# Schematic.net
KiCad netlist of a schematic drawn in EAGLE
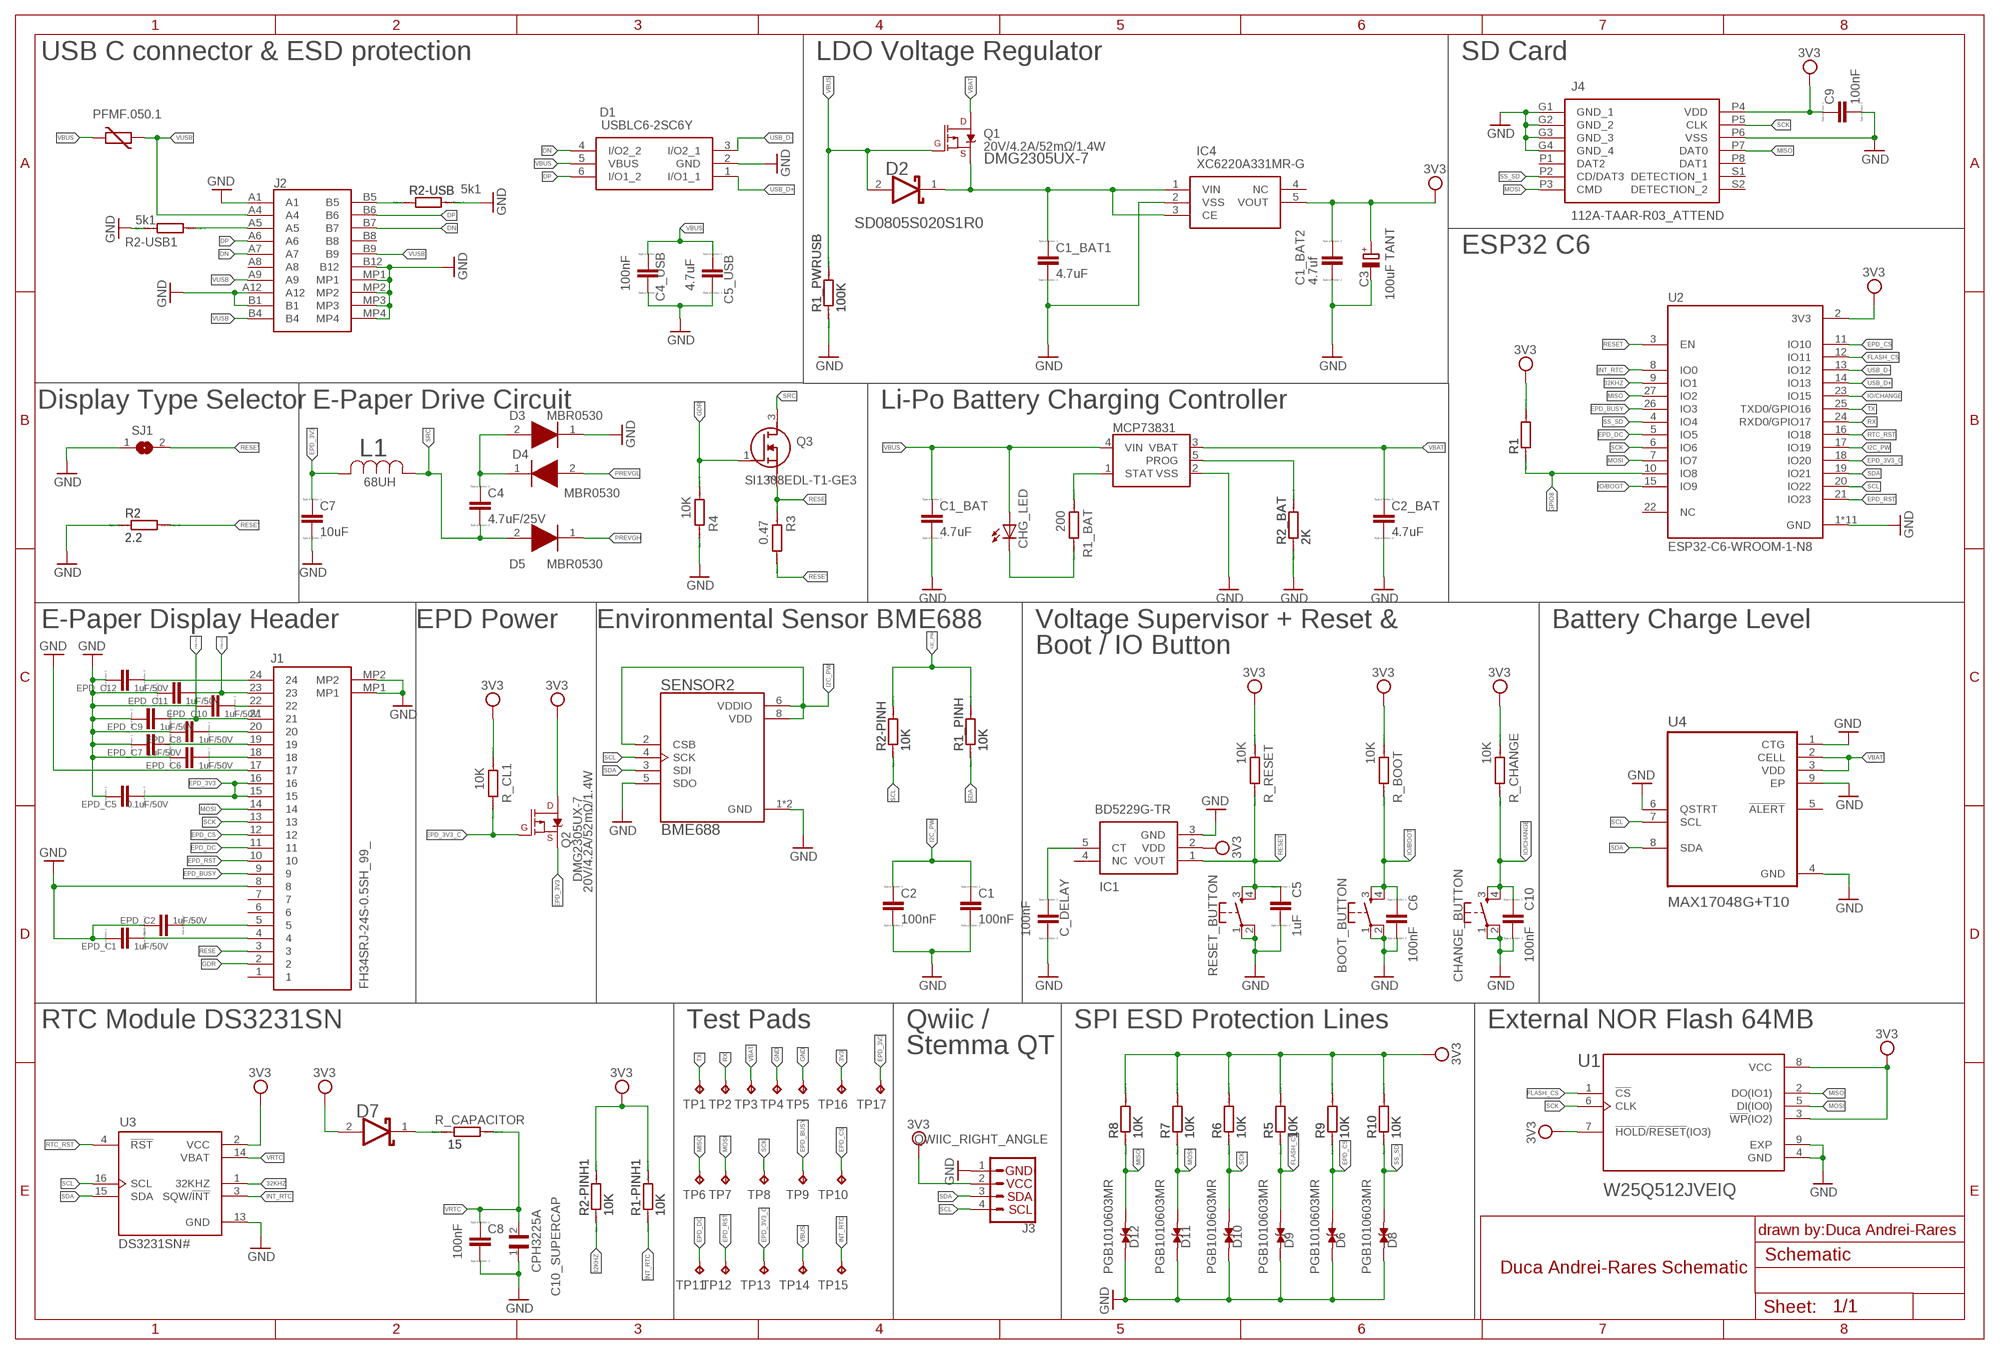
[diagram p0: schematic, sheet 1]

(export (version "E")
  (design (tool "Eeschema 10.0.6"))
  (components
    (comp (ref "BOOT_BUTTON")
      (value "BUTTON_CUSYOMV1")
      (footprint "eagle-import:MYBUTTON")
      (libsource (lib "eagle-import") (part "BUTTON_CUSYOMV1"))
    )
    (comp (ref "C1")
      (value "100nF")
      (footprint "eagle-import:EAGLE-LTSPICE_C0402")
      (libsource (lib "eagle-import") (part "EAGLE-LTSPICE_CC0402"))
    )
    (comp (ref "C1_BAT")
      (value "4.7uF")
      (footprint "eagle-import:EAGLE-LTSPICE_C0402")
      (libsource (lib "eagle-import") (part "EAGLE-LTSPICE_CC0402"))
    )
    (comp (ref "C1_BAT1")
      (value "4.7uF")
      (footprint "eagle-import:EAGLE-LTSPICE_C0402")
      (libsource (lib "eagle-import") (part "EAGLE-LTSPICE_CC0402"))
    )
    (comp (ref "C1_BAT2")
      (value "4.7uf")
      (footprint "eagle-import:EAGLE-LTSPICE_C0402")
      (libsource (lib "eagle-import") (part "EAGLE-LTSPICE_CC0402"))
    )
    (comp (ref "C2")
      (value "100nF")
      (footprint "eagle-import:EAGLE-LTSPICE_C0402")
      (libsource (lib "eagle-import") (part "EAGLE-LTSPICE_CC0402"))
    )
    (comp (ref "C2_BAT")
      (value "4.7uF")
      (footprint "eagle-import:EAGLE-LTSPICE_C0402")
      (libsource (lib "eagle-import") (part "EAGLE-LTSPICE_CC0402"))
    )
    (comp (ref "C3")
      (value "100uF TANT")
      (footprint "eagle-import:RCL_CT3528")
      (libsource (lib "eagle-import") (part "RCL_CPOL-EUCT3528"))
    )
    (comp (ref "C4")
      (value "4.7uF/25V")
      (footprint "eagle-import:EAGLE-LTSPICE_C0402")
      (libsource (lib "eagle-import") (part "EAGLE-LTSPICE_CC0402"))
    )
    (comp (ref "C4_USB")
      (value "100nF")
      (footprint "eagle-import:EAGLE-LTSPICE_C0402")
      (libsource (lib "eagle-import") (part "EAGLE-LTSPICE_CC0402"))
    )
    (comp (ref "C5")
      (value "1uF")
      (footprint "eagle-import:EAGLE-LTSPICE_C0402")
      (libsource (lib "eagle-import") (part "EAGLE-LTSPICE_CC0402"))
    )
    (comp (ref "C5_USB")
      (value "4.7uF")
      (footprint "eagle-import:EAGLE-LTSPICE_C0402")
      (libsource (lib "eagle-import") (part "EAGLE-LTSPICE_CC0402"))
    )
    (comp (ref "C6")
      (value "100nF")
      (footprint "eagle-import:EAGLE-LTSPICE_C0402")
      (libsource (lib "eagle-import") (part "EAGLE-LTSPICE_CC0402"))
    )
    (comp (ref "C7")
      (value "10uF")
      (footprint "eagle-import:EAGLE-LTSPICE_C0402")
      (libsource (lib "eagle-import") (part "EAGLE-LTSPICE_CC0402"))
    )
    (comp (ref "C8")
      (value "100nF")
      (footprint "eagle-import:EAGLE-LTSPICE_C0402")
      (libsource (lib "eagle-import") (part "EAGLE-LTSPICE_CC0402"))
    )
    (comp (ref "C9")
      (value "100nF")
      (footprint "eagle-import:EAGLE-LTSPICE_C0402")
      (libsource (lib "eagle-import") (part "EAGLE-LTSPICE_CC0402"))
    )
    (comp (ref "C10")
      (value "100nF")
      (footprint "eagle-import:EAGLE-LTSPICE_C0402")
      (libsource (lib "eagle-import") (part "EAGLE-LTSPICE_CC0402"))
    )
    (comp (ref "C10_SUPERCAP")
      (value "CPH3225A")
      (footprint "eagle-import:CAPCP3225X100N")
      (fields (field (name "MF") "Seiko Instruments"))
      (libsource (lib "eagle-import") (part "CPH3225A"))
    )
    (comp (ref "CHANGE_BUTTON")
      (value "BUTTON_CUSYOMV1")
      (footprint "eagle-import:MYBUTTON")
      (libsource (lib "eagle-import") (part "BUTTON_CUSYOMV1"))
    )
    (comp (ref "CHG_LED")
      (value "ADAFRUIT_LEDCHIP-LED0603")
      (footprint "eagle-import:ADAFRUIT_CHIP-LED0603")
      (libsource (lib "eagle-import") (part "ADAFRUIT_LEDCHIP-LED0603"))
    )
    (comp (ref "C_DELAY")
      (value "100nF")
      (footprint "eagle-import:EAGLE-LTSPICE_C0402")
      (libsource (lib "eagle-import") (part "EAGLE-LTSPICE_CC0402"))
    )
    (comp (ref "D1")
      (value "USBLC6-2SC6Y")
      (footprint "eagle-import:SOT95P280X145-6N")
      (fields (field (name "MF") "STMicroelectronics"))
      (libsource (lib "eagle-import") (part "USBLC6-2SC6Y"))
    )
    (comp (ref "D2")
      (value "SD0805S020S1R0")
      (footprint "eagle-import:ESP32_WROVER_AVX---SD0805S020S1R0_AVX_SD0805S020S1R0_0")
      (fields
        (field (name "DIGIKEY_PART_NUMBER") "478-7800-1-ND")
        (field (name "MF") "AVX")
        (field (name "MOUSER_PART_NUMBER") "581-SD0805S020S1R0")
        (field (name "SD0805S020S1R0") "SD0805S020S1R0")
      )
      (libsource (lib "eagle-import") (part "ESP32_WROVER_AVX---SD0805S020S1R0_AVX_SD0805S020S1R0_0_0AVX_SD0805S020S1R0_0_0"))
    )
    (comp (ref "D3")
      (value "MBR0530")
      (footprint "eagle-import:SOD3716X135N")
      (fields (field (name "MF") "ON Semiconductor"))
      (libsource (lib "eagle-import") (part "MBR0530"))
    )
    (comp (ref "D4")
      (value "MBR0530")
      (footprint "eagle-import:SOD3716X135N")
      (fields (field (name "MF") "ON Semiconductor"))
      (libsource (lib "eagle-import") (part "MBR0530"))
    )
    (comp (ref "D5")
      (value "MBR0530")
      (footprint "eagle-import:SOD3716X135N")
      (fields (field (name "MF") "ON Semiconductor"))
      (libsource (lib "eagle-import") (part "MBR0530"))
    )
    (comp (ref "D6")
      (value "PGB1010603MR")
      (footprint "eagle-import:DIOC1608X36N")
      (fields (field (name "MF") "Littelfuse Inc."))
      (libsource (lib "eagle-import") (part "PGB1010603MR"))
    )
    (comp (ref "D7")
      (value "ESP32_WROVER_AVX---SD0805S020S1R0_AVX_SD0805S020S1R0_0_0AVX_SD0805S020S1R0_0_0")
      (footprint "eagle-import:ESP32_WROVER_AVX---SD0805S020S1R0_AVX_SD0805S020S1R0_0")
      (fields
        (field (name "DIGIKEY_PART_NUMBER") "478-7800-1-ND")
        (field (name "MF") "AVX")
        (field (name "MOUSER_PART_NUMBER") "581-SD0805S020S1R0")
      )
      (libsource (lib "eagle-import") (part "ESP32_WROVER_AVX---SD0805S020S1R0_AVX_SD0805S020S1R0_0_0AVX_SD0805S020S1R0_0_0"))
    )
    (comp (ref "D8")
      (value "PGB1010603MR")
      (footprint "eagle-import:DIOC1608X36N")
      (fields (field (name "MF") "Littelfuse Inc."))
      (libsource (lib "eagle-import") (part "PGB1010603MR"))
    )
    (comp (ref "D9")
      (value "PGB1010603MR")
      (footprint "eagle-import:DIOC1608X36N")
      (fields (field (name "MF") "Littelfuse Inc."))
      (libsource (lib "eagle-import") (part "PGB1010603MR"))
    )
    (comp (ref "D10")
      (value "PGB1010603MR")
      (footprint "eagle-import:DIOC1608X36N")
      (fields (field (name "MF") "Littelfuse Inc."))
      (libsource (lib "eagle-import") (part "PGB1010603MR"))
    )
    (comp (ref "D11")
      (value "PGB1010603MR")
      (footprint "eagle-import:DIOC1608X36N")
      (fields (field (name "MF") "Littelfuse Inc."))
      (libsource (lib "eagle-import") (part "PGB1010603MR"))
    )
    (comp (ref "D12")
      (value "PGB1010603MR")
      (footprint "eagle-import:DIOC1608X36N")
      (fields (field (name "MF") "Littelfuse Inc."))
      (libsource (lib "eagle-import") (part "PGB1010603MR"))
    )
    (comp (ref "EPD_C1")
      (value "1uF/50V")
      (footprint "eagle-import:EAGLE-LTSPICE_C0402")
      (libsource (lib "eagle-import") (part "EAGLE-LTSPICE_CC0402"))
    )
    (comp (ref "EPD_C2")
      (value "1uF/50V")
      (footprint "eagle-import:EAGLE-LTSPICE_C0402")
      (libsource (lib "eagle-import") (part "EAGLE-LTSPICE_CC0402"))
    )
    (comp (ref "EPD_C5")
      (value "0.1uF/50V")
      (footprint "eagle-import:EAGLE-LTSPICE_C0402")
      (libsource (lib "eagle-import") (part "EAGLE-LTSPICE_CC0402"))
    )
    (comp (ref "EPD_C6")
      (value "1uF/50V")
      (footprint "eagle-import:EAGLE-LTSPICE_C0402")
      (libsource (lib "eagle-import") (part "EAGLE-LTSPICE_CC0402"))
    )
    (comp (ref "EPD_C7")
      (value "1uF/50V")
      (footprint "eagle-import:EAGLE-LTSPICE_C0402")
      (libsource (lib "eagle-import") (part "EAGLE-LTSPICE_CC0402"))
    )
    (comp (ref "EPD_C8")
      (value "1uF/50V")
      (footprint "eagle-import:EAGLE-LTSPICE_C0402")
      (libsource (lib "eagle-import") (part "EAGLE-LTSPICE_CC0402"))
    )
    (comp (ref "EPD_C9")
      (value "1uF/50V")
      (footprint "eagle-import:EAGLE-LTSPICE_C0402")
      (libsource (lib "eagle-import") (part "EAGLE-LTSPICE_CC0402"))
    )
    (comp (ref "EPD_C10")
      (value "1uF/50V")
      (footprint "eagle-import:EAGLE-LTSPICE_C0402")
      (libsource (lib "eagle-import") (part "EAGLE-LTSPICE_CC0402"))
    )
    (comp (ref "EPD_C11")
      (value "1uF/50V")
      (footprint "eagle-import:EAGLE-LTSPICE_C0402")
      (libsource (lib "eagle-import") (part "EAGLE-LTSPICE_CC0402"))
    )
    (comp (ref "EPD_C12")
      (value "1uF/50V")
      (footprint "eagle-import:EAGLE-LTSPICE_C0402")
      (libsource (lib "eagle-import") (part "EAGLE-LTSPICE_CC0402"))
    )
    (comp (ref "IC1")
      (value "BD5229G-TR")
      (footprint "eagle-import:SOT95P280X125-5N")
      (fields (field (name "MOUSER_PART_NUMBER") "755-BD5229G-TR"))
      (libsource (lib "eagle-import") (part "BD5229G-TR"))
    )
    (comp (ref "IC4")
      (value "XC6220A331MR-G")
      (footprint "eagle-import:SOT95P280X120-5N")
      (fields (field (name "MOUSER_PART_NUMBER") "865-XC6220A331MR-G"))
      (libsource (lib "eagle-import") (part "XC6220A331MR-G"))
    )
    (comp (ref "J1")
      (value "FH34SRJ-24S-0.5SH_99_")
      (footprint "eagle-import:FH34SRJ24S05SH99")
      (fields
        (field (name "MANUFACTURER_PART_NUMBER") "FH34SRJ-24S-0.5SH(99)")
        (field (name "MOUSER_PART_NUMBER") "798-FH34SRJ24S05SH99")
      )
      (libsource (lib "eagle-import") (part "FH34SRJ-24S-0.5SH_99_"))
    )
    (comp (ref "J2")
      (value "SAMACSYS_PARTS_USB4110-GF-A")
      (footprint "eagle-import:SAMACSYS_PARTS_USB4110GFA")
      (fields
        (field (name "MANUFACTURER_PART_NUMBER") "USB4110-GF-A")
        (field (name "MOUSER_PART_NUMBER") "640-USB4110-GF-A")
      )
      (libsource (lib "eagle-import") (part "SAMACSYS_PARTS_USB4110-GF-A"))
    )
    (comp (ref "J3")
      (value "QWIIC_RIGHT_ANGLE")
      (footprint "eagle-import:JST04_1MM_RA")
      (libsource (lib "eagle-import") (part "QWIIC_CONNECTORJS-1MM"))
    )
    (comp (ref "J4")
      (value "112A-TAAR-R03_ATTEND")
      (footprint "eagle-import:112ATAARR03ATTEND")
      (fields (field (name "MANUFACTURER_PART_NUMBER") "112A-TAAR-R03 ATTEND"))
      (libsource (lib "eagle-import") (part "112A-TAAR-R03_ATTEND"))
    )
    (comp (ref "L1")
      (value "744043680IND_4828-WE-TPC_WRE")
      (footprint "eagle-import:IND_4828-WE-TPC_WRE")
      (fields
        (field (name "MANUFACTURER_PART_NUMBER") "744043680")
        (field (name "68UH") "68UH")
        (field (name "COPYRIGHT") "Copyright (C) 2024 Ultra Librarian. All rights reserved.")
      )
      (libsource (lib "eagle-import") (part "744043680IND_4828-WE-TPC_WRE"))
    )
    (comp (ref "MCP73831")
      (value "ESP32_WROVER_SPARKFUN-IC-POWER_MCP73831")
      (footprint "eagle-import:ESP32_WROVER_SPARKFUN-IC-POWER_SOT23-5")
      (libsource (lib "eagle-import") (part "ESP32_WROVER_SPARKFUN-IC-POWER_MCP73831"))
    )
    (comp (ref "PFMF.050.1")
      (value "ESP32C6_VARISTORCN1812")
      (footprint "eagle-import:ESP32C6_VARISTOR_CT_CN1812")
      (libsource (lib "eagle-import") (part "ESP32C6_VARISTORCN1812"))
    )
    (comp (ref "Q1")
      (value "20V/4.2A/52mΩ/1.4W")
      (footprint "eagle-import:ESP32_WROVER_SPARKFUN-DISCRETESEMI_SOT23-3")
      (fields (field (name "DMG2305UX-7") "DMG2305UX-7"))
      (libsource (lib "eagle-import") (part "ESP32_WROVER_SPARKFUN-DISCRETESEMI_MOSFET_PCH-DMG2305UX-7"))
    )
    (comp (ref "Q2")
      (value "20V/4.2A/52mΩ/1.4W")
      (footprint "eagle-import:ESP32_WROVER_SPARKFUN-DISCRETESEMI_SOT23-3")
      (fields (field (name "DMG2305UX-7") "DMG2305UX-7"))
      (libsource (lib "eagle-import") (part "ESP32_WROVER_SPARKFUN-DISCRETESEMI_MOSFET_PCH-DMG2305UX-7"))
    )
    (comp (ref "Q3")
      (value "SI1308EDL-T1-GE3")
      (footprint "eagle-import:SOT65P210X110-3N")
      (fields (field (name "MF") "Vishay Siliconix"))
      (libsource (lib "eagle-import") (part "SI1308EDL-T1-GE3"))
    )
    (comp (ref "R1")
      (value "ESP32_WROVER_EAGLE-LTSPICE_RR0402")
      (footprint "eagle-import:ESP32_WROVER_EAGLE-LTSPICE_R0402")
      (libsource (lib "eagle-import") (part "ESP32_WROVER_EAGLE-LTSPICE_RR0402"))
    )
    (comp (ref "R1-PINH1")
      (value "10K")
      (footprint "eagle-import:ESP32_WROVER_EAGLE-LTSPICE_R0402")
      (libsource (lib "eagle-import") (part "ESP32_WROVER_EAGLE-LTSPICE_RR0402"))
    )
    (comp (ref "R1_BAT")
      (value "200")
      (footprint "eagle-import:ESP32_WROVER_EAGLE-LTSPICE_R0402")
      (libsource (lib "eagle-import") (part "ESP32_WROVER_EAGLE-LTSPICE_RR0402"))
    )
    (comp (ref "R1_PINH")
      (value "10K")
      (footprint "eagle-import:ESP32_WROVER_EAGLE-LTSPICE_R0402")
      (libsource (lib "eagle-import") (part "ESP32_WROVER_EAGLE-LTSPICE_RR0402"))
    )
    (comp (ref "R1_PWRUSB")
      (value "100K")
      (footprint "eagle-import:ESP32_WROVER_EAGLE-LTSPICE_R0402")
      (fields (field (name "PWRUSB") "PWRUSB"))
      (libsource (lib "eagle-import") (part "ESP32_WROVER_EAGLE-LTSPICE_RR0402"))
    )
    (comp (ref "R2")
      (value "2.2")
      (footprint "eagle-import:ESP32_WROVER_EAGLE-LTSPICE_R0402")
      (libsource (lib "eagle-import") (part "ESP32_WROVER_EAGLE-LTSPICE_RR0402"))
    )
    (comp (ref "R2-PINH")
      (value "10K")
      (footprint "eagle-import:ESP32_WROVER_EAGLE-LTSPICE_R0402")
      (libsource (lib "eagle-import") (part "ESP32_WROVER_EAGLE-LTSPICE_RR0402"))
    )
    (comp (ref "R2-PINH1")
      (value "10K")
      (footprint "eagle-import:ESP32_WROVER_EAGLE-LTSPICE_R0402")
      (libsource (lib "eagle-import") (part "ESP32_WROVER_EAGLE-LTSPICE_RR0402"))
    )
    (comp (ref "R2-USB")
      (value "5k1")
      (footprint "eagle-import:ESP32_WROVER_EAGLE-LTSPICE_R0402")
      (libsource (lib "eagle-import") (part "ESP32_WROVER_EAGLE-LTSPICE_RR0402"))
    )
    (comp (ref "R2-USB1")
      (value "5k1")
      (footprint "eagle-import:ESP32_WROVER_EAGLE-LTSPICE_R0402")
      (libsource (lib "eagle-import") (part "ESP32_WROVER_EAGLE-LTSPICE_RR0402"))
    )
    (comp (ref "R2_BAT")
      (value "2K")
      (footprint "eagle-import:ESP32_WROVER_EAGLE-LTSPICE_R0402")
      (libsource (lib "eagle-import") (part "ESP32_WROVER_EAGLE-LTSPICE_RR0402"))
    )
    (comp (ref "R3")
      (value "0.47")
      (footprint "eagle-import:ESP32_WROVER_EAGLE-LTSPICE_R0402")
      (libsource (lib "eagle-import") (part "ESP32_WROVER_EAGLE-LTSPICE_RR0402"))
    )
    (comp (ref "R4")
      (value "10K")
      (footprint "eagle-import:ESP32_WROVER_EAGLE-LTSPICE_R0402")
      (libsource (lib "eagle-import") (part "ESP32_WROVER_EAGLE-LTSPICE_RR0402"))
    )
    (comp (ref "R5")
      (value "10K")
      (footprint "eagle-import:ESP32_WROVER_EAGLE-LTSPICE_R0402")
      (libsource (lib "eagle-import") (part "ESP32_WROVER_EAGLE-LTSPICE_RR0402"))
    )
    (comp (ref "R6")
      (value "10K")
      (footprint "eagle-import:ESP32_WROVER_EAGLE-LTSPICE_R0402")
      (libsource (lib "eagle-import") (part "ESP32_WROVER_EAGLE-LTSPICE_RR0402"))
    )
    (comp (ref "R7")
      (value "10K")
      (footprint "eagle-import:ESP32_WROVER_EAGLE-LTSPICE_R0402")
      (libsource (lib "eagle-import") (part "ESP32_WROVER_EAGLE-LTSPICE_RR0402"))
    )
    (comp (ref "R8")
      (value "10K")
      (footprint "eagle-import:ESP32_WROVER_EAGLE-LTSPICE_R0402")
      (libsource (lib "eagle-import") (part "ESP32_WROVER_EAGLE-LTSPICE_RR0402"))
    )
    (comp (ref "R9")
      (value "10K")
      (footprint "eagle-import:ESP32_WROVER_EAGLE-LTSPICE_R0402")
      (libsource (lib "eagle-import") (part "ESP32_WROVER_EAGLE-LTSPICE_RR0402"))
    )
    (comp (ref "R10")
      (value "10K")
      (footprint "eagle-import:ESP32_WROVER_EAGLE-LTSPICE_R0402")
      (libsource (lib "eagle-import") (part "ESP32_WROVER_EAGLE-LTSPICE_RR0402"))
    )
    (comp (ref "RESET_BUTTON")
      (value "BUTTON_CUSYOMV1")
      (footprint "eagle-import:MYBUTTON")
      (libsource (lib "eagle-import") (part "BUTTON_CUSYOMV1"))
    )
    (comp (ref "R_BOOT")
      (value "10K")
      (footprint "eagle-import:ESP32_WROVER_EAGLE-LTSPICE_R0402")
      (libsource (lib "eagle-import") (part "ESP32_WROVER_EAGLE-LTSPICE_RR0402"))
    )
    (comp (ref "R_CAPACITOR")
      (value "15")
      (footprint "eagle-import:ESP32_WROVER_EAGLE-LTSPICE_R0402")
      (libsource (lib "eagle-import") (part "ESP32_WROVER_EAGLE-LTSPICE_RR0402"))
    )
    (comp (ref "R_CHANGE")
      (value "10K")
      (footprint "eagle-import:ESP32_WROVER_EAGLE-LTSPICE_R0402")
      (libsource (lib "eagle-import") (part "ESP32_WROVER_EAGLE-LTSPICE_RR0402"))
    )
    (comp (ref "R_CL1")
      (value "10K")
      (footprint "eagle-import:ESP32_WROVER_EAGLE-LTSPICE_R0402")
      (libsource (lib "eagle-import") (part "ESP32_WROVER_EAGLE-LTSPICE_RR0402"))
    )
    (comp (ref "R_RESET")
      (value "10K")
      (footprint "eagle-import:ESP32_WROVER_EAGLE-LTSPICE_R0402")
      (libsource (lib "eagle-import") (part "ESP32_WROVER_EAGLE-LTSPICE_RR0402"))
    )
    (comp (ref "SENSOR2")
      (value "ESP32_WROVER_BME680_BME680")
      (footprint "eagle-import:ESP32_WROVER_BME680_PSON80P300X300X100-8N")
      (fields
        (field (name "MF") "Bosch Sensortec")
        (field (name "MP") "BME680")
        (field (name "BME688") "BME688")
      )
      (libsource (lib "eagle-import") (part "ESP32_WROVER_BME680_BME680"))
    )
    (comp (ref "SJ1") (value "SJ") (footprint "eagle-import:SJ") (libsource (lib "eagle-import") (part "SJ")))
    (comp (ref "TP1")
      (value "TPTP20R")
      (footprint "eagle-import:TP20R")
      (libsource (lib "eagle-import") (part "TPTP20R"))
    )
    (comp (ref "TP2")
      (value "TPTP20R")
      (footprint "eagle-import:TP20R")
      (libsource (lib "eagle-import") (part "TPTP20R"))
    )
    (comp (ref "TP3")
      (value "TPTP20R")
      (footprint "eagle-import:TP20R")
      (libsource (lib "eagle-import") (part "TPTP20R"))
    )
    (comp (ref "TP4")
      (value "TPTP20R")
      (footprint "eagle-import:TP20R")
      (libsource (lib "eagle-import") (part "TPTP20R"))
    )
    (comp (ref "TP5")
      (value "TPTP20R")
      (footprint "eagle-import:TP20R")
      (libsource (lib "eagle-import") (part "TPTP20R"))
    )
    (comp (ref "TP6")
      (value "TPTP20R")
      (footprint "eagle-import:TP20R")
      (libsource (lib "eagle-import") (part "TPTP20R"))
    )
    (comp (ref "TP7")
      (value "TPTP20R")
      (footprint "eagle-import:TP20R")
      (libsource (lib "eagle-import") (part "TPTP20R"))
    )
    (comp (ref "TP8")
      (value "TPTP20R")
      (footprint "eagle-import:TP20R")
      (libsource (lib "eagle-import") (part "TPTP20R"))
    )
    (comp (ref "TP9")
      (value "TPTP20R")
      (footprint "eagle-import:TP20R")
      (libsource (lib "eagle-import") (part "TPTP20R"))
    )
    (comp (ref "TP10")
      (value "TPTP20R")
      (footprint "eagle-import:TP20R")
      (libsource (lib "eagle-import") (part "TPTP20R"))
    )
    (comp (ref "TP11")
      (value "TPTP20R")
      (footprint "eagle-import:TP20R")
      (libsource (lib "eagle-import") (part "TPTP20R"))
    )
    (comp (ref "TP12")
      (value "TPTP20R")
      (footprint "eagle-import:TP20R")
      (libsource (lib "eagle-import") (part "TPTP20R"))
    )
    (comp (ref "TP13")
      (value "TPTP20R")
      (footprint "eagle-import:TP20R")
      (libsource (lib "eagle-import") (part "TPTP20R"))
    )
    (comp (ref "TP14")
      (value "TPTP20R")
      (footprint "eagle-import:TP20R")
      (libsource (lib "eagle-import") (part "TPTP20R"))
    )
    (comp (ref "TP15")
      (value "TPTP20R")
      (footprint "eagle-import:TP20R")
      (libsource (lib "eagle-import") (part "TPTP20R"))
    )
    (comp (ref "TP16")
      (value "TPTP20R")
      (footprint "eagle-import:TP20R")
      (libsource (lib "eagle-import") (part "TPTP20R"))
    )
    (comp (ref "TP17")
      (value "TPTP20R")
      (footprint "eagle-import:TP20R")
      (libsource (lib "eagle-import") (part "TPTP20R"))
    )
    (comp (ref "U1")
      (value "W25Q512JVEIQ")
      (footprint "eagle-import:SON127P600X800X80-9N")
      (fields (field (name "MF") "Winbond Electronics"))
      (libsource (lib "eagle-import") (part "W25Q512JVEIQ"))
    )
    (comp (ref "U2")
      (value "ESP32-C6-WROOM-1-N8")
      (footprint "eagle-import:XCVR_ESP32-C6-WROOM-1-N8")
      (fields (field (name "MF") "Espressif Systems"))
      (libsource (lib "eagle-import") (part "ESP32-C6-WROOM-1-N8"))
    )
    (comp (ref "U3")
      (value "DS3231SN#")
      (footprint "eagle-import:SOIC127P1032X265-16N")
      (fields (field (name "MF") "Analog Devices"))
      (libsource (lib "eagle-import") (part "DS3231SN#"))
    )
    (comp (ref "U4")
      (value "MAX17048G+T10")
      (footprint "eagle-import:SON50P200X200X80-9N")
      (fields (field (name "MF") "Analog Devices"))
      (libsource (lib "eagle-import") (part "MAX17048G+T10"))
    )
  )
  (nets
    (net (code "1") (name "3V3") (class "Default")
      (node (ref "C1_BAT2") (pin "1") (pinfunction "1_1") (pintype "passive"))
      (node (ref "C3") (pin "+") (pinfunction "+_+") (pintype "passive"))
      (node (ref "C9") (pin "1") (pinfunction "1_1") (pintype "passive"))
      (node (ref "D7") (pin "2") (pinfunction "ANODE_2") (pintype "bidirectional"))
      (node (ref "IC1") (pin "2") (pinfunction "VDD_2") (pintype "bidirectional"))
      (node (ref "IC4") (pin "5") (pinfunction "VOUT_5") (pintype "bidirectional"))
      (node (ref "J3") (pin "2") (pinfunction "2_2") (pintype "power_in"))
      (node (ref "J4") (pin "P4") (pinfunction "VDD_P4") (pintype "bidirectional"))
      (node (ref "Q2") (pin "3") (pinfunction "D_3") (pintype "bidirectional"))
      (node (ref "R1") (pin "2") (pinfunction "2_2") (pintype "passive"))
      (node (ref "R1-PINH1") (pin "2") (pinfunction "2_2") (pintype "passive"))
      (node (ref "R10") (pin "2") (pinfunction "2_2") (pintype "passive"))
      (node (ref "R2-PINH1") (pin "2") (pinfunction "2_2") (pintype "passive"))
      (node (ref "R5") (pin "2") (pinfunction "2_2") (pintype "passive"))
      (node (ref "R6") (pin "2") (pinfunction "2_2") (pintype "passive"))
      (node (ref "R7") (pin "2") (pinfunction "2_2") (pintype "passive"))
      (node (ref "R8") (pin "2") (pinfunction "2_2") (pintype "passive"))
      (node (ref "R9") (pin "2") (pinfunction "2_2") (pintype "passive"))
      (node (ref "R_BOOT") (pin "2") (pinfunction "2_2") (pintype "passive"))
      (node (ref "R_CHANGE") (pin "2") (pinfunction "2_2") (pintype "passive"))
      (node (ref "R_CL1") (pin "2") (pinfunction "2_2") (pintype "passive"))
      (node (ref "R_RESET") (pin "2") (pinfunction "2_2") (pintype "passive"))
      (node (ref "TP16") (pin "TP") (pinfunction "TP_TP") (pintype "input"))
      (node (ref "U1") (pin "3") (pinfunction "~{WP}(IO2)_3") (pintype "bidirectional"))
      (node (ref "U1") (pin "7") (pinfunction "~{HOLD}/~{RESET}(IO3)_7") (pintype "bidirectional"))
      (node (ref "U1") (pin "8") (pinfunction "VCC_8") (pintype "power_in"))
      (node (ref "U2") (pin "2") (pinfunction "3V3_2") (pintype "power_in"))
      (node (ref "U3") (pin "2") (pinfunction "VCC_2") (pintype "power_in"))
    )
    (net (code "2") (name "32KHZ") (class "Default")
      (node (ref "R2-PINH1") (pin "1") (pinfunction "1_1") (pintype "passive"))
      (node (ref "U2") (pin "9") (pinfunction "IO1_9") (pintype "bidirectional"))
      (node (ref "U3") (pin "1") (pinfunction "32KHZ_1") (pintype "output"))
    )
    (net (code "3") (name "DN") (class "Default")
      (node (ref "D1") (pin "4") (pinfunction "I/O2_2_4") (pintype "bidirectional"))
      (node (ref "J2") (pin "A7") (pinfunction "A7_A7") (pintype "bidirectional"))
      (node (ref "J2") (pin "B7") (pinfunction "B7_B7") (pintype "bidirectional"))
    )
    (net (code "4") (name "DP") (class "Default")
      (node (ref "D1") (pin "6") (pinfunction "I/O1_2_6") (pintype "bidirectional"))
      (node (ref "J2") (pin "A6") (pinfunction "A6_A6") (pintype "bidirectional"))
      (node (ref "J2") (pin "B6") (pinfunction "B6_B6") (pintype "bidirectional"))
    )
    (net (code "5") (name "EPD_3V3") (class "Default")
      (node (ref "C7") (pin "1") (pinfunction "1_1") (pintype "passive"))
      (node (ref "EPD_C5") (pin "2") (pinfunction "2_2") (pintype "passive"))
      (node (ref "J1") (pin "15") (pinfunction "15_15") (pintype "bidirectional"))
      (node (ref "J1") (pin "16") (pinfunction "16_16") (pintype "bidirectional"))
      (node (ref "L1") (pin "2") (pinfunction "2_2") (pintype "passive"))
      (node (ref "Q2") (pin "2") (pinfunction "S_2") (pintype "bidirectional"))
      (node (ref "TP17") (pin "TP") (pinfunction "TP_TP") (pintype "input"))
    )
    (net (code "6") (name "EPD_3V3_C") (class "Default")
      (node (ref "Q2") (pin "1") (pinfunction "G_1") (pintype "bidirectional"))
      (node (ref "R_CL1") (pin "1") (pinfunction "1_1") (pintype "passive"))
      (node (ref "TP13") (pin "TP") (pinfunction "TP_TP") (pintype "input"))
      (node (ref "U2") (pin "18") (pinfunction "IO20_18") (pintype "bidirectional"))
    )
    (net (code "7") (name "EPD_BUSY") (class "Default")
      (node (ref "J1") (pin "9") (pinfunction "9_9") (pintype "bidirectional"))
      (node (ref "TP9") (pin "TP") (pinfunction "TP_TP") (pintype "input"))
      (node (ref "U2") (pin "26") (pinfunction "IO3_26") (pintype "bidirectional"))
    )
    (net (code "8") (name "EPD_CS") (class "Default")
      (node (ref "D6") (pin "2") (pinfunction "2_2") (pintype "passive"))
      (node (ref "J1") (pin "12") (pinfunction "12_12") (pintype "bidirectional"))
      (node (ref "R9") (pin "1") (pinfunction "1_1") (pintype "passive"))
      (node (ref "TP10") (pin "TP") (pinfunction "TP_TP") (pintype "input"))
      (node (ref "U2") (pin "11") (pinfunction "IO10_11") (pintype "bidirectional"))
    )
    (net (code "9") (name "EPD_DC") (class "Default")
      (node (ref "J1") (pin "11") (pinfunction "11_11") (pintype "bidirectional"))
      (node (ref "TP11") (pin "TP") (pinfunction "TP_TP") (pintype "input"))
      (node (ref "U2") (pin "5") (pinfunction "IO5_5") (pintype "bidirectional"))
    )
    (net (code "10") (name "EPD_RST") (class "Default")
      (node (ref "J1") (pin "10") (pinfunction "10_10") (pintype "bidirectional"))
      (node (ref "TP12") (pin "TP") (pinfunction "TP_TP") (pintype "input"))
      (node (ref "U2") (pin "21") (pinfunction "IO23_21") (pintype "bidirectional"))
    )
    (net (code "11") (name "FLASH_CS") (class "Default")
      (node (ref "D9") (pin "2") (pinfunction "2_2") (pintype "passive"))
      (node (ref "R5") (pin "1") (pinfunction "1_1") (pintype "passive"))
      (node (ref "U1") (pin "1") (pinfunction "~{CS}_1") (pintype "input"))
      (node (ref "U2") (pin "12") (pinfunction "IO11_12") (pintype "bidirectional"))
    )
    (net (code "12") (name "GDR") (class "Default")
      (node (ref "J1") (pin "2") (pinfunction "2_2") (pintype "bidirectional"))
      (node (ref "Q3") (pin "1") (pinfunction "G_1") (pintype "bidirectional"))
      (node (ref "R4") (pin "2") (pinfunction "2_2") (pintype "passive"))
    )
    (net (code "13") (name "GND") (class "Default")
      (node (ref "BOOT_BUTTON") (pin "1") (pinfunction "1_1") (pintype "passive"))
      (node (ref "BOOT_BUTTON") (pin "2") (pinfunction "2_2") (pintype "passive"))
      (node (ref "C1") (pin "2") (pinfunction "2_2") (pintype "passive"))
      (node (ref "C10") (pin "2") (pinfunction "2_2") (pintype "passive"))
      (node (ref "C10_SUPERCAP") (pin "1") (pinfunction "1_1") (pintype "passive"))
      (node (ref "C1_BAT") (pin "2") (pinfunction "2_2") (pintype "passive"))
      (node (ref "C1_BAT1") (pin "2") (pinfunction "2_2") (pintype "passive"))
      (node (ref "C1_BAT2") (pin "2") (pinfunction "2_2") (pintype "passive"))
      (node (ref "C2") (pin "2") (pinfunction "2_2") (pintype "passive"))
      (node (ref "C2_BAT") (pin "2") (pinfunction "2_2") (pintype "passive"))
      (node (ref "C3") (pin "-") (pinfunction "-_-") (pintype "passive"))
      (node (ref "C4_USB") (pin "2") (pinfunction "2_2") (pintype "passive"))
      (node (ref "C5") (pin "2") (pinfunction "2_2") (pintype "passive"))
      (node (ref "C5_USB") (pin "2") (pinfunction "2_2") (pintype "passive"))
      (node (ref "C6") (pin "2") (pinfunction "2_2") (pintype "passive"))
      (node (ref "C7") (pin "2") (pinfunction "2_2") (pintype "passive"))
      (node (ref "C8") (pin "2") (pinfunction "2_2") (pintype "passive"))
      (node (ref "C9") (pin "2") (pinfunction "2_2") (pintype "passive"))
      (node (ref "CHANGE_BUTTON") (pin "1") (pinfunction "1_1") (pintype "passive"))
      (node (ref "CHANGE_BUTTON") (pin "2") (pinfunction "2_2") (pintype "passive"))
      (node (ref "C_DELAY") (pin "2") (pinfunction "2_2") (pintype "passive"))
      (node (ref "D1") (pin "2") (pinfunction "GND_2") (pintype "bidirectional"))
      (node (ref "D10") (pin "1") (pinfunction "1_1") (pintype "passive"))
      (node (ref "D11") (pin "1") (pinfunction "1_1") (pintype "passive"))
      (node (ref "D12") (pin "1") (pinfunction "1_1") (pintype "passive"))
      (node (ref "D3") (pin "1") (pinfunction "K_1") (pintype "bidirectional"))
      (node (ref "D6") (pin "1") (pinfunction "1_1") (pintype "passive"))
      (node (ref "D8") (pin "1") (pinfunction "1_1") (pintype "passive"))
      (node (ref "D9") (pin "1") (pinfunction "1_1") (pintype "passive"))
      (node (ref "EPD_C1") (pin "1") (pinfunction "1_1") (pintype "passive"))
      (node (ref "EPD_C10") (pin "1") (pinfunction "1_1") (pintype "passive"))
      (node (ref "EPD_C11") (pin "1") (pinfunction "1_1") (pintype "passive"))
      (node (ref "EPD_C12") (pin "1") (pinfunction "1_1") (pintype "passive"))
      (node (ref "EPD_C2") (pin "1") (pinfunction "1_1") (pintype "passive"))
      (node (ref "EPD_C5") (pin "1") (pinfunction "1_1") (pintype "passive"))
      (node (ref "EPD_C6") (pin "1") (pinfunction "1_1") (pintype "passive"))
      (node (ref "EPD_C7") (pin "1") (pinfunction "1_1") (pintype "passive"))
      (node (ref "EPD_C8") (pin "1") (pinfunction "1_1") (pintype "passive"))
      (node (ref "EPD_C9") (pin "1") (pinfunction "1_1") (pintype "passive"))
      (node (ref "IC1") (pin "3") (pinfunction "GND_3") (pintype "bidirectional"))
      (node (ref "IC4") (pin "2") (pinfunction "VSS_2") (pintype "bidirectional"))
      (node (ref "J1") (pin "17") (pinfunction "17_17") (pintype "bidirectional"))
      (node (ref "J1") (pin "8") (pinfunction "8_8") (pintype "bidirectional"))
      (node (ref "J1") (pin "MP1") (pinfunction "MP1_MP1") (pintype "bidirectional"))
      (node (ref "J1") (pin "MP2") (pinfunction "MP2_MP2") (pintype "bidirectional"))
      (node (ref "J2") (pin "A1") (pinfunction "A1_A1") (pintype "bidirectional"))
      (node (ref "J2") (pin "A12") (pinfunction "A12_A12") (pintype "bidirectional"))
      (node (ref "J2") (pin "B1") (pinfunction "B1_B1") (pintype "bidirectional"))
      (node (ref "J2") (pin "B12") (pinfunction "B12_B12") (pintype "bidirectional"))
      (node (ref "J2") (pin "MP1") (pinfunction "MP1_MP1") (pintype "bidirectional"))
      (node (ref "J2") (pin "MP2") (pinfunction "MP2_MP2") (pintype "bidirectional"))
      (node (ref "J2") (pin "MP3") (pinfunction "MP3_MP3") (pintype "bidirectional"))
      (node (ref "J2") (pin "MP4") (pinfunction "MP4_MP4") (pintype "bidirectional"))
      (node (ref "J3") (pin "1") (pinfunction "1_1") (pintype "power_in"))
      (node (ref "J4") (pin "G1") (pinfunction "GND_1_G1") (pintype "bidirectional"))
      (node (ref "J4") (pin "G2") (pinfunction "GND_2_G2") (pintype "bidirectional"))
      (node (ref "J4") (pin "G3") (pinfunction "GND_3_G3") (pintype "bidirectional"))
      (node (ref "J4") (pin "G4") (pinfunction "GND_4_G4") (pintype "bidirectional"))
      (node (ref "J4") (pin "P6") (pinfunction "VSS_P6") (pintype "bidirectional"))
      (node (ref "MCP73831") (pin "2") (pinfunction "VSS_2") (pintype "power_in"))
      (node (ref "R1_PWRUSB") (pin "1") (pinfunction "1_1") (pintype "passive"))
      (node (ref "R2") (pin "1") (pinfunction "1_1") (pintype "passive"))
      (node (ref "R2-USB") (pin "2") (pinfunction "2_2") (pintype "passive"))
      (node (ref "R2-USB1") (pin "1") (pinfunction "1_1") (pintype "passive"))
      (node (ref "R2_BAT") (pin "1") (pinfunction "1_1") (pintype "passive"))
      (node (ref "R4") (pin "1") (pinfunction "1_1") (pintype "passive"))
      (node (ref "RESET_BUTTON") (pin "1") (pinfunction "1_1") (pintype "passive"))
      (node (ref "RESET_BUTTON") (pin "2") (pinfunction "2_2") (pintype "passive"))
      (node (ref "SENSOR2") (pin "1") (pinfunction "GND_1") (pintype "power_in"))
      (node (ref "SENSOR2") (pin "5") (pinfunction "SDO_5") (pintype "bidirectional"))
      (node (ref "SENSOR2") (pin "7") (pinfunction "GND_7") (pintype "power_in"))
      (node (ref "SJ1") (pin "1") (pinfunction "1_1") (pintype "passive"))
      (node (ref "TP4") (pin "TP") (pinfunction "TP_TP") (pintype "input"))
      (node (ref "TP5") (pin "TP") (pinfunction "TP_TP") (pintype "input"))
      (node (ref "U1") (pin "4") (pinfunction "GND_4") (pintype "power_in"))
      (node (ref "U1") (pin "9") (pinfunction "EXP_9") (pintype "passive"))
      (node (ref "U2") (pin "1") (pinfunction "GND_1") (pintype "power_in"))
      (node (ref "U2") (pin "28") (pinfunction "GND_28") (pintype "power_in"))
      (node (ref "U2") (pin "29_1") (pinfunction "GND_29_1") (pintype "power_in"))
      (node (ref "U2") (pin "29_2") (pinfunction "GND_29_2") (pintype "power_in"))
      (node (ref "U2") (pin "29_3") (pinfunction "GND_29_3") (pintype "power_in"))
      (node (ref "U2") (pin "29_4") (pinfunction "GND_29_4") (pintype "power_in"))
      (node (ref "U2") (pin "29_5") (pinfunction "GND_29_5") (pintype "power_in"))
      (node (ref "U2") (pin "29_6") (pinfunction "GND_29_6") (pintype "power_in"))
      (node (ref "U2") (pin "29_7") (pinfunction "GND_29_7") (pintype "power_in"))
      (node (ref "U2") (pin "29_8") (pinfunction "GND_29_8") (pintype "power_in"))
      (node (ref "U2") (pin "29_9") (pinfunction "GND_29_9") (pintype "power_in"))
      (node (ref "U3") (pin "13") (pinfunction "GND_13") (pintype "power_in"))
      (node (ref "U4") (pin "1") (pinfunction "CTG_1") (pintype "power_in"))
      (node (ref "U4") (pin "4") (pinfunction "GND_4") (pintype "power_in"))
      (node (ref "U4") (pin "6") (pinfunction "QSTRT_6") (pintype "input"))
      (node (ref "U4") (pin "9") (pinfunction "EP_9") (pintype "power_in"))
    )
    (net (code "14") (name "GPIO8") (class "Default")
      (node (ref "R1") (pin "1") (pinfunction "1_1") (pintype "passive"))
      (node (ref "U2") (pin "10") (pinfunction "IO8_10") (pintype "bidirectional"))
    )
    (net (code "15") (name "I2C_PW") (class "Default")
      (node (ref "C1") (pin "1") (pinfunction "1_1") (pintype "passive"))
      (node (ref "C2") (pin "1") (pinfunction "1_1") (pintype "passive"))
      (node (ref "R1_PINH") (pin "2") (pinfunction "2_2") (pintype "passive"))
      (node (ref "R2-PINH") (pin "2") (pinfunction "2_2") (pintype "passive"))
      (node (ref "SENSOR2") (pin "2") (pinfunction "CSB_2") (pintype "input"))
      (node (ref "SENSOR2") (pin "6") (pinfunction "VDDIO_6") (pintype "power_in"))
      (node (ref "SENSOR2") (pin "8") (pinfunction "VDD_8") (pintype "power_in"))
      (node (ref "U2") (pin "17") (pinfunction "IO19_17") (pintype "bidirectional"))
    )
    (net (code "16") (name "INT_RTC") (class "Default")
      (node (ref "R1-PINH1") (pin "1") (pinfunction "1_1") (pintype "passive"))
      (node (ref "TP15") (pin "TP") (pinfunction "TP_TP") (pintype "input"))
      (node (ref "U2") (pin "8") (pinfunction "IO0_8") (pintype "bidirectional"))
      (node (ref "U3") (pin "3") (pinfunction "SQW/~{INT}_3") (pintype "output"))
    )
    (net (code "17") (name "IO{slash}BOOT") (class "Default")
      (node (ref "BOOT_BUTTON") (pin "3") (pinfunction "3_3") (pintype "passive"))
      (node (ref "BOOT_BUTTON") (pin "4") (pinfunction "4_4") (pintype "passive"))
      (node (ref "C6") (pin "1") (pinfunction "1_1") (pintype "passive"))
      (node (ref "R_BOOT") (pin "1") (pinfunction "1_1") (pintype "passive"))
      (node (ref "U2") (pin "15") (pinfunction "IO9_15") (pintype "bidirectional"))
    )
    (net (code "18") (name "IO{slash}CHANGE") (class "Default")
      (node (ref "C10") (pin "1") (pinfunction "1_1") (pintype "passive"))
      (node (ref "CHANGE_BUTTON") (pin "3") (pinfunction "3_3") (pintype "passive"))
      (node (ref "CHANGE_BUTTON") (pin "4") (pinfunction "4_4") (pintype "passive"))
      (node (ref "R_CHANGE") (pin "1") (pinfunction "1_1") (pintype "passive"))
      (node (ref "U2") (pin "23") (pinfunction "IO15_23") (pintype "bidirectional"))
    )
    (net (code "19") (name "MISO") (class "Default")
      (node (ref "D12") (pin "2") (pinfunction "2_2") (pintype "passive"))
      (node (ref "J4") (pin "P7") (pinfunction "DAT0_P7") (pintype "bidirectional"))
      (node (ref "R8") (pin "1") (pinfunction "1_1") (pintype "passive"))
      (node (ref "TP6") (pin "TP") (pinfunction "TP_TP") (pintype "input"))
      (node (ref "U1") (pin "2") (pinfunction "DO(IO1)_2") (pintype "bidirectional"))
      (node (ref "U2") (pin "27") (pinfunction "IO2_27") (pintype "bidirectional"))
    )
    (net (code "20") (name "MOSI") (class "Default")
      (node (ref "D11") (pin "2") (pinfunction "2_2") (pintype "passive"))
      (node (ref "J1") (pin "14") (pinfunction "14_14") (pintype "bidirectional"))
      (node (ref "J4") (pin "P3") (pinfunction "CMD_P3") (pintype "bidirectional"))
      (node (ref "R7") (pin "1") (pinfunction "1_1") (pintype "passive"))
      (node (ref "TP7") (pin "TP") (pinfunction "TP_TP") (pintype "input"))
      (node (ref "U1") (pin "5") (pinfunction "DI(IO0)_5") (pintype "bidirectional"))
      (node (ref "U2") (pin "7") (pinfunction "IO7_7") (pintype "bidirectional"))
    )
    (net (code "21") (name "Net-(CHG_LED-PadC)") (class "Default")
      (node (ref "CHG_LED") (pin "C") (pinfunction "C_C") (pintype "passive"))
      (node (ref "R1_BAT") (pin "1") (pinfunction "1_1") (pintype "passive"))
    )
    (net (code "22") (name "Net-(D2-CATHODE)") (class "Default")
      (node (ref "C1_BAT1") (pin "1") (pinfunction "1_1") (pintype "passive"))
      (node (ref "D2") (pin "1") (pinfunction "CATHODE_1") (pintype "bidirectional"))
      (node (ref "IC4") (pin "1") (pinfunction "VIN_1") (pintype "bidirectional"))
      (node (ref "IC4") (pin "3") (pinfunction "CE_3") (pintype "bidirectional"))
      (node (ref "Q1") (pin "2") (pinfunction "S_2") (pintype "bidirectional"))
    )
    (net (code "23") (name "Net-(D3-A)") (class "Default")
      (node (ref "C4") (pin "1") (pinfunction "1_1") (pintype "passive"))
      (node (ref "D3") (pin "2") (pinfunction "A_2") (pintype "bidirectional"))
      (node (ref "D4") (pin "1") (pinfunction "K_1") (pintype "bidirectional"))
    )
    (net (code "24") (name "Net-(D7-CATHODE)") (class "Default")
      (node (ref "D7") (pin "1") (pinfunction "CATHODE_1") (pintype "bidirectional"))
      (node (ref "R_CAPACITOR") (pin "1") (pinfunction "1_1") (pintype "passive"))
    )
    (net (code "25") (name "Net-(EPD_C1-Pad2)") (class "Default")
      (node (ref "EPD_C1") (pin "2") (pinfunction "2_2") (pintype "passive"))
      (node (ref "J1") (pin "4") (pinfunction "4_4") (pintype "bidirectional"))
    )
    (net (code "26") (name "Net-(EPD_C2-Pad2)") (class "Default")
      (node (ref "EPD_C2") (pin "2") (pinfunction "2_2") (pintype "passive"))
      (node (ref "J1") (pin "5") (pinfunction "5_5") (pintype "bidirectional"))
    )
    (net (code "27") (name "Net-(EPD_C6-Pad2)") (class "Default")
      (node (ref "EPD_C6") (pin "2") (pinfunction "2_2") (pintype "passive"))
      (node (ref "J1") (pin "18") (pinfunction "18_18") (pintype "bidirectional"))
    )
    (net (code "28") (name "Net-(EPD_C7-Pad2)") (class "Default")
      (node (ref "EPD_C7") (pin "2") (pinfunction "2_2") (pintype "passive"))
      (node (ref "J1") (pin "19") (pinfunction "19_19") (pintype "bidirectional"))
    )
    (net (code "29") (name "Net-(EPD_C8-Pad2)") (class "Default")
      (node (ref "EPD_C8") (pin "2") (pinfunction "2_2") (pintype "passive"))
      (node (ref "J1") (pin "20") (pinfunction "20_20") (pintype "bidirectional"))
    )
    (net (code "30") (name "Net-(EPD_C10-Pad2)") (class "Default")
      (node (ref "EPD_C10") (pin "2") (pinfunction "2_2") (pintype "passive"))
      (node (ref "J1") (pin "22") (pinfunction "22_22") (pintype "bidirectional"))
    )
    (net (code "31") (name "Net-(EPD_C12-Pad2)") (class "Default")
      (node (ref "EPD_C12") (pin "2") (pinfunction "2_2") (pintype "passive"))
      (node (ref "J1") (pin "24") (pinfunction "24_24") (pintype "bidirectional"))
    )
    (net (code "32") (name "Net-(IC1-CT)") (class "Default")
      (node (ref "C_DELAY") (pin "1") (pinfunction "1_1") (pintype "passive"))
      (node (ref "IC1") (pin "5") (pinfunction "CT_5") (pintype "bidirectional"))
    )
    (net (code "33") (name "Net-(J2-PadA5)") (class "Default")
      (node (ref "J2") (pin "A5") (pinfunction "A5_A5") (pintype "bidirectional"))
      (node (ref "R2-USB1") (pin "2") (pinfunction "2_2") (pintype "passive"))
    )
    (net (code "34") (name "Net-(J2-PadB5)") (class "Default")
      (node (ref "J2") (pin "B5") (pinfunction "B5_B5") (pintype "bidirectional"))
      (node (ref "R2-USB") (pin "1") (pinfunction "1_1") (pintype "passive"))
    )
    (net (code "35") (name "Net-(MCP73831-PROG)") (class "Default")
      (node (ref "MCP73831") (pin "5") (pinfunction "PROG_5") (pintype "input"))
      (node (ref "R2_BAT") (pin "2") (pinfunction "2_2") (pintype "passive"))
    )
    (net (code "36") (name "Net-(MCP73831-STAT)") (class "Default")
      (node (ref "MCP73831") (pin "1") (pinfunction "STAT_1") (pintype "output"))
      (node (ref "R1_BAT") (pin "2") (pinfunction "2_2") (pintype "passive"))
    )
    (net (code "37") (name "PREVGH") (class "Default")
      (node (ref "D5") (pin "1") (pinfunction "K_1") (pintype "bidirectional"))
      (node (ref "EPD_C9") (pin "2") (pinfunction "2_2") (pintype "passive"))
      (node (ref "J1") (pin "21") (pinfunction "21_21") (pintype "bidirectional"))
    )
    (net (code "38") (name "PREVGL") (class "Default")
      (node (ref "D4") (pin "2") (pinfunction "A_2") (pintype "bidirectional"))
      (node (ref "EPD_C11") (pin "2") (pinfunction "2_2") (pintype "passive"))
      (node (ref "J1") (pin "23") (pinfunction "23_23") (pintype "bidirectional"))
    )
    (net (code "39") (name "RESE") (class "Default")
      (node (ref "J1") (pin "3") (pinfunction "3_3") (pintype "bidirectional"))
      (node (ref "Q3") (pin "2") (pinfunction "S_2") (pintype "bidirectional"))
      (node (ref "R3") (pin "2") (pinfunction "2_2") (pintype "passive"))
    )
    (net (code "40") (name "RESE'") (class "Default")
      (node (ref "R2") (pin "2") (pinfunction "2_2") (pintype "passive"))
      (node (ref "R3") (pin "1") (pinfunction "1_1") (pintype "passive"))
      (node (ref "SJ1") (pin "2") (pinfunction "2_2") (pintype "passive"))
    )
    (net (code "41") (name "RESET") (class "Default")
      (node (ref "C5") (pin "1") (pinfunction "1_1") (pintype "passive"))
      (node (ref "IC1") (pin "1") (pinfunction "VOUT_1") (pintype "bidirectional"))
      (node (ref "RESET_BUTTON") (pin "3") (pinfunction "3_3") (pintype "passive"))
      (node (ref "RESET_BUTTON") (pin "4") (pinfunction "4_4") (pintype "passive"))
      (node (ref "R_RESET") (pin "1") (pinfunction "1_1") (pintype "passive"))
      (node (ref "U2") (pin "3") (pinfunction "EN_3") (pintype "input"))
    )
    (net (code "42") (name "RTC_RST") (class "Default")
      (node (ref "U2") (pin "16") (pinfunction "IO18_16") (pintype "bidirectional"))
      (node (ref "U3") (pin "4") (pinfunction "~{RST}_4") (pintype "input"))
    )
    (net (code "43") (name "RX") (class "Default")
      (node (ref "TP2") (pin "TP") (pinfunction "TP_TP") (pintype "input"))
      (node (ref "U2") (pin "24") (pinfunction "RXD0/GPIO17_24") (pintype "bidirectional"))
    )
    (net (code "44") (name "SCK") (class "Default")
      (node (ref "D10") (pin "2") (pinfunction "2_2") (pintype "passive"))
      (node (ref "J1") (pin "13") (pinfunction "13_13") (pintype "bidirectional"))
      (node (ref "J4") (pin "P5") (pinfunction "CLK_P5") (pintype "bidirectional"))
      (node (ref "R6") (pin "1") (pinfunction "1_1") (pintype "passive"))
      (node (ref "TP8") (pin "TP") (pinfunction "TP_TP") (pintype "input"))
      (node (ref "U1") (pin "6") (pinfunction "CLK_6") (pintype "input"))
      (node (ref "U2") (pin "6") (pinfunction "IO6_6") (pintype "bidirectional"))
    )
    (net (code "45") (name "SCL") (class "Default")
      (node (ref "J3") (pin "4") (pinfunction "4_4") (pintype "passive"))
      (node (ref "R2-PINH") (pin "1") (pinfunction "1_1") (pintype "passive"))
      (node (ref "SENSOR2") (pin "4") (pinfunction "SCK_4") (pintype "input"))
      (node (ref "U2") (pin "20") (pinfunction "IO22_20") (pintype "bidirectional"))
      (node (ref "U3") (pin "16") (pinfunction "SCL_16") (pintype "input"))
      (node (ref "U4") (pin "7") (pinfunction "SCL_7") (pintype "input"))
    )
    (net (code "46") (name "SDA") (class "Default")
      (node (ref "J3") (pin "3") (pinfunction "3_3") (pintype "passive"))
      (node (ref "R1_PINH") (pin "1") (pinfunction "1_1") (pintype "passive"))
      (node (ref "SENSOR2") (pin "3") (pinfunction "SDI_3") (pintype "bidirectional"))
      (node (ref "U2") (pin "19") (pinfunction "IO21_19") (pintype "bidirectional"))
      (node (ref "U3") (pin "15") (pinfunction "SDA_15") (pintype "bidirectional"))
      (node (ref "U4") (pin "8") (pinfunction "SDA_8") (pintype "bidirectional"))
    )
    (net (code "47") (name "SRC") (class "Default")
      (node (ref "C4") (pin "2") (pinfunction "2_2") (pintype "passive"))
      (node (ref "D5") (pin "2") (pinfunction "A_2") (pintype "bidirectional"))
      (node (ref "L1") (pin "1") (pinfunction "1_1") (pintype "passive"))
      (node (ref "Q3") (pin "3") (pinfunction "D_3") (pintype "bidirectional"))
    )
    (net (code "48") (name "SS_SD") (class "Default")
      (node (ref "D8") (pin "2") (pinfunction "2_2") (pintype "passive"))
      (node (ref "J4") (pin "P2") (pinfunction "CD/DAT3_P2") (pintype "bidirectional"))
      (node (ref "R10") (pin "1") (pinfunction "1_1") (pintype "passive"))
      (node (ref "U2") (pin "4") (pinfunction "IO4_4") (pintype "bidirectional"))
    )
    (net (code "49") (name "TX") (class "Default")
      (node (ref "TP1") (pin "TP") (pinfunction "TP_TP") (pintype "input"))
      (node (ref "U2") (pin "25") (pinfunction "TXD0/GPIO16_25") (pintype "bidirectional"))
    )
    (net (code "50") (name "USB_D+") (class "Default")
      (node (ref "D1") (pin "1") (pinfunction "I/O1_1_1") (pintype "bidirectional"))
      (node (ref "U2") (pin "14") (pinfunction "IO13_14") (pintype "bidirectional"))
    )
    (net (code "51") (name "USB_D-") (class "Default")
      (node (ref "D1") (pin "3") (pinfunction "I/O2_1_3") (pintype "bidirectional"))
      (node (ref "U2") (pin "13") (pinfunction "IO12_13") (pintype "bidirectional"))
    )
    (net (code "52") (name "VBAT") (class "Default")
      (node (ref "C2_BAT") (pin "1") (pinfunction "1_1") (pintype "passive"))
      (node (ref "MCP73831") (pin "3") (pinfunction "VBAT_3") (pintype "power_in"))
      (node (ref "Q1") (pin "3") (pinfunction "D_3") (pintype "bidirectional"))
      (node (ref "TP3") (pin "TP") (pinfunction "TP_TP") (pintype "input"))
      (node (ref "U4") (pin "2") (pinfunction "CELL_2") (pintype "power_in"))
      (node (ref "U4") (pin "3") (pinfunction "VDD_3") (pintype "power_in"))
    )
    (net (code "53") (name "VBUS") (class "Default")
      (node (ref "C1_BAT") (pin "1") (pinfunction "1_1") (pintype "passive"))
      (node (ref "C4_USB") (pin "1") (pinfunction "1_1") (pintype "passive"))
      (node (ref "C5_USB") (pin "1") (pinfunction "1_1") (pintype "passive"))
      (node (ref "CHG_LED") (pin "A") (pinfunction "A_A") (pintype "passive"))
      (node (ref "D1") (pin "5") (pinfunction "VBUS_5") (pintype "bidirectional"))
      (node (ref "D2") (pin "2") (pinfunction "ANODE_2") (pintype "bidirectional"))
      (node (ref "MCP73831") (pin "4") (pinfunction "VIN_4") (pintype "power_in"))
      (node (ref "PFMF.050.1") (pin "2") (pinfunction "2_2") (pintype "passive"))
      (node (ref "Q1") (pin "1") (pinfunction "G_1") (pintype "bidirectional"))
      (node (ref "R1_PWRUSB") (pin "2") (pinfunction "2_2") (pintype "passive"))
      (node (ref "TP14") (pin "TP") (pinfunction "TP_TP") (pintype "input"))
    )
    (net (code "54") (name "VRTC") (class "Default")
      (node (ref "C10_SUPERCAP") (pin "2") (pinfunction "2_2") (pintype "passive"))
      (node (ref "C8") (pin "1") (pinfunction "1_1") (pintype "passive"))
      (node (ref "R_CAPACITOR") (pin "2") (pinfunction "2_2") (pintype "passive"))
      (node (ref "U3") (pin "14") (pinfunction "VBAT_14") (pintype "power_in"))
    )
    (net (code "55") (name "VUSB") (class "Default")
      (node (ref "J2") (pin "A4") (pinfunction "A4_A4") (pintype "bidirectional"))
      (node (ref "J2") (pin "A9") (pinfunction "A9_A9") (pintype "bidirectional"))
      (node (ref "J2") (pin "B4") (pinfunction "B4_B4") (pintype "bidirectional"))
      (node (ref "J2") (pin "B9") (pinfunction "B9_B9") (pintype "bidirectional"))
      (node (ref "PFMF.050.1") (pin "1") (pinfunction "1_1") (pintype "passive"))
    )
    (net (code "56") (name "unconnected-(IC1-NC-Pad4)") (class "Default")
      (node (ref "IC1") (pin "4") (pinfunction "NC_4") (pintype "no_connect"))
    )
    (net (code "57") (name "unconnected-(IC4-NC-Pad4)") (class "Default")
      (node (ref "IC4") (pin "4") (pinfunction "NC_4") (pintype "no_connect"))
    )
    (net (code "58") (name "unconnected-(J1-Pad1)") (class "Default")
      (node (ref "J1") (pin "1") (pinfunction "1_1") (pintype "bidirectional"))
    )
    (net (code "59") (name "unconnected-(J1-Pad6)") (class "Default")
      (node (ref "J1") (pin "6") (pinfunction "6_6") (pintype "bidirectional"))
    )
    (net (code "60") (name "unconnected-(J1-Pad7)") (class "Default")
      (node (ref "J1") (pin "7") (pinfunction "7_7") (pintype "bidirectional"))
    )
    (net (code "61") (name "unconnected-(J2-PadA8)") (class "Default")
      (node (ref "J2") (pin "A8") (pinfunction "A8_A8") (pintype "bidirectional"))
    )
    (net (code "62") (name "unconnected-(J2-PadB8)") (class "Default")
      (node (ref "J2") (pin "B8") (pinfunction "B8_B8") (pintype "bidirectional"))
    )
    (net (code "63") (name "unconnected-(J4-DAT1-PadP8)") (class "Default")
      (node (ref "J4") (pin "P8") (pinfunction "DAT1_P8") (pintype "bidirectional"))
    )
    (net (code "64") (name "unconnected-(J4-DAT2-PadP1)") (class "Default")
      (node (ref "J4") (pin "P1") (pinfunction "DAT2_P1") (pintype "bidirectional"))
    )
    (net (code "65") (name "unconnected-(J4-DETECTION_1-PadS1)") (class "Default")
      (node (ref "J4") (pin "S1") (pinfunction "DETECTION_1_S1") (pintype "bidirectional"))
    )
    (net (code "66") (name "unconnected-(J4-DETECTION_2-PadS2)") (class "Default")
      (node (ref "J4") (pin "S2") (pinfunction "DETECTION_2_S2") (pintype "bidirectional"))
    )
    (net (code "67") (name "unconnected-(U2-NC-Pad22)") (class "Default")
      (node (ref "U2") (pin "22") (pinfunction "NC_22") (pintype "no_connect"))
    )
    (net (code "68") (name "unconnected-(U4-~{ALERT}-Pad5)") (class "Default")
      (node (ref "U4") (pin "5") (pinfunction "~{ALERT}_5") (pintype "output"))
    )
  )
)
